# 2810_driverBoard.net
KiCad netlist of a schematic drawn in EasyEDA Pro
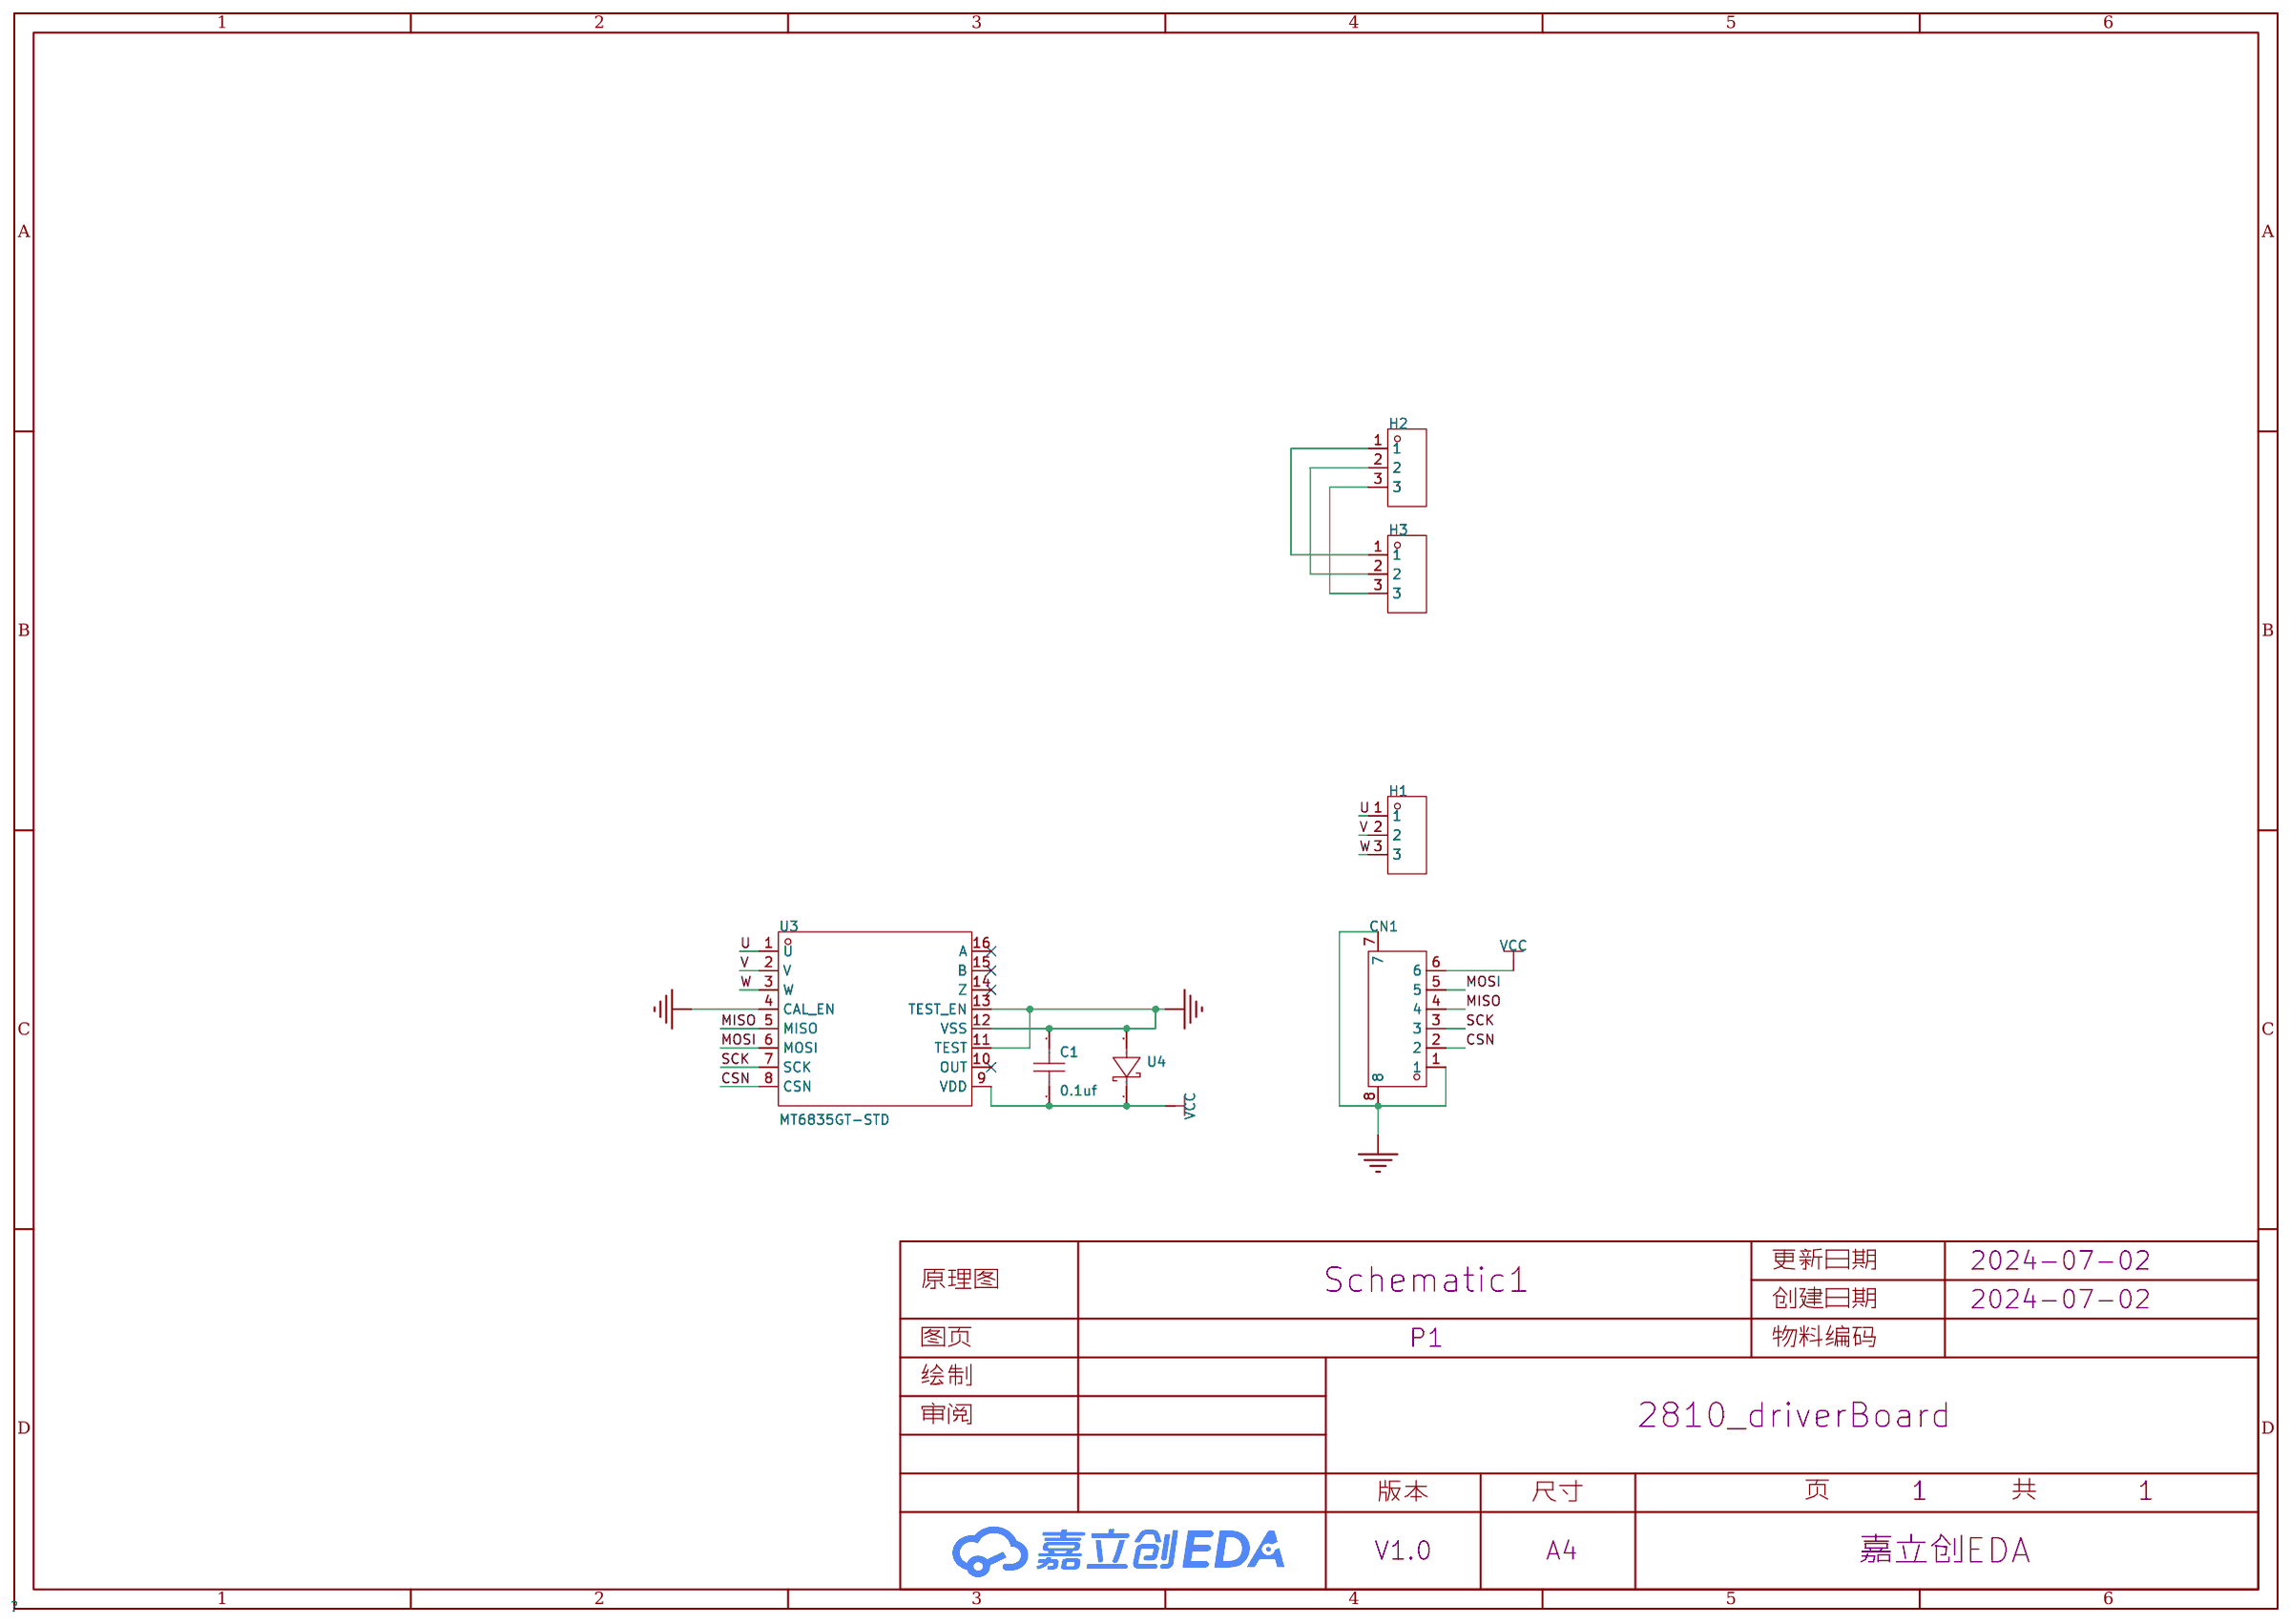
[diagram p0: schematic sheet]

(export (version "E")
  (design (tool "Eeschema 10.0.6"))
  (components
    (comp (ref "C1")
      (value "0.1uf")
      (footprint "easyedapro:C0603")
      (libsource (lib "easyedapro") (part "CapAcitance"))
    )
    (comp (ref "CN1")
      (value "M1010RS-06P")
      (footprint "easyedapro:CONN-SMD_M1010RS-06P")
      (description "插针结构:1x6P;间距:1mm;安装方式:卧贴;参考系列:-;总PIN数:6P;排数:1;每排PIN数:6;行距:-;额定电流:1A;工作温度范围:-25°C~+85°C;")
      (fields (field (name "Manufacturer") "XFCN(兴飞)"))
      (libsource (lib "easyedapro") (part "M1010RS-06P"))
    )
    (comp (ref "H1")
      (value "PZ254V-11-03P")
      (footprint "easyedapro:HDR-TH_3P-P2.54-V-M")
      (fields (field (name "Manufacturer") "XFCN(兴飞)"))
      (libsource (lib "easyedapro") (part "PZ254V-11-03P_C2937625"))
    )
    (comp (ref "H2")
      (value "PZ254V-11-03P")
      (footprint "easyedapro:HDR-TH_3P-P2.54-V-M")
      (fields (field (name "Manufacturer") "XFCN(兴飞)"))
      (libsource (lib "easyedapro") (part "PZ254V-11-03P_C2937625"))
    )
    (comp (ref "H3")
      (value "PZ254V-11-03P")
      (footprint "easyedapro:HDR-TH_3P-P2.54-V-M")
      (fields (field (name "Manufacturer") "XFCN(兴飞)"))
      (libsource (lib "easyedapro") (part "PZ254V-11-03P_C2937625"))
    )
    (comp (ref "U3")
      (value "MT6835GT-STD")
      (footprint "easyedapro:TSSOP-16_L5.0-W4.4-P0.65-LS6.4-BL")
      (fields (field (name "Manufacturer") "MagnTek(麦歌恩)"))
      (libsource (lib "easyedapro") (part "MT6835GT-STD"))
    )
    (comp (ref "U4")
      (value "PTVS6V0S1UR")
      (footprint "easyedapro:SOD-123_L2.7-W1.6-LS3.7-RD")
      (fields (field (name "Manufacturer") "FUXINSEMI(富芯森美)"))
      (libsource (lib "easyedapro") (part "PTVS6V0S1UR_C18723426"))
    )
  )
  (nets
    (net (code "1") (name "/CSN") (class "Default")
      (node (ref "CN1") (pin "2") (pinfunction "2_2") (pintype "unspecified"))
      (node (ref "U3") (pin "8") (pinfunction "CSN_8") (pintype "unspecified"))
    )
    (net (code "2") (name "/MISO") (class "Default")
      (node (ref "CN1") (pin "4") (pinfunction "4_4") (pintype "unspecified"))
      (node (ref "U3") (pin "5") (pinfunction "MISO_5") (pintype "unspecified"))
    )
    (net (code "3") (name "/MOSI") (class "Default")
      (node (ref "CN1") (pin "5") (pinfunction "5_5") (pintype "unspecified"))
      (node (ref "U3") (pin "6") (pinfunction "MOSI_6") (pintype "unspecified"))
    )
    (net (code "4") (name "/SCK") (class "Default")
      (node (ref "CN1") (pin "3") (pinfunction "3_3") (pintype "unspecified"))
      (node (ref "U3") (pin "7") (pinfunction "SCK_7") (pintype "unspecified"))
    )
    (net (code "5") (name "/U") (class "Default")
      (node (ref "H1") (pin "1") (pinfunction "1_1") (pintype "unspecified"))
      (node (ref "U3") (pin "1") (pinfunction "U_1") (pintype "unspecified"))
    )
    (net (code "6") (name "/V") (class "Default")
      (node (ref "H1") (pin "2") (pinfunction "2_2") (pintype "unspecified"))
      (node (ref "U3") (pin "2") (pinfunction "V_2") (pintype "unspecified"))
    )
    (net (code "7") (name "/W") (class "Default")
      (node (ref "H1") (pin "3") (pinfunction "3_3") (pintype "unspecified"))
      (node (ref "U3") (pin "3") (pinfunction "W_3") (pintype "unspecified"))
    )
    (net (code "8") (name "GND") (class "Default")
      (node (ref "C1") (pin "2") (pinfunction "2_2") (pintype "input"))
      (node (ref "CN1") (pin "1") (pinfunction "1_1") (pintype "unspecified"))
      (node (ref "CN1") (pin "7") (pinfunction "7_7") (pintype "unspecified"))
      (node (ref "CN1") (pin "8") (pinfunction "8_8") (pintype "unspecified"))
      (node (ref "U3") (pin "11") (pinfunction "TEST_11") (pintype "unspecified"))
      (node (ref "U3") (pin "12") (pinfunction "VSS_12") (pintype "unspecified"))
      (node (ref "U3") (pin "13") (pinfunction "TEST_EN_13") (pintype "unspecified"))
      (node (ref "U3") (pin "4") (pinfunction "CAL_EN_4") (pintype "unspecified"))
      (node (ref "U4") (pin "2") (pinfunction "A_2") (pintype "unspecified"))
    )
    (net (code "9") (name "Net-(H2-Pad1)") (class "Default")
      (node (ref "H2") (pin "1") (pinfunction "1_1") (pintype "unspecified"))
      (node (ref "H3") (pin "1") (pinfunction "1_1") (pintype "unspecified"))
    )
    (net (code "10") (name "Net-(H2-Pad2)") (class "Default")
      (node (ref "H2") (pin "2") (pinfunction "2_2") (pintype "unspecified"))
      (node (ref "H3") (pin "2") (pinfunction "2_2") (pintype "unspecified"))
    )
    (net (code "11") (name "Net-(H2-Pad3)") (class "Default")
      (node (ref "H2") (pin "3") (pinfunction "3_3") (pintype "unspecified"))
      (node (ref "H3") (pin "3") (pinfunction "3_3") (pintype "unspecified"))
    )
    (net (code "12") (name "VCC") (class "Default")
      (node (ref "C1") (pin "1") (pinfunction "1_1") (pintype "input"))
      (node (ref "CN1") (pin "6") (pinfunction "6_6") (pintype "unspecified"))
      (node (ref "U3") (pin "9") (pinfunction "VDD_9") (pintype "unspecified"))
      (node (ref "U4") (pin "1") (pinfunction "K_1") (pintype "unspecified"))
    )
    (net (code "13") (name "unconnected-(U3-A-Pad16)") (class "Default")
      (node (ref "U3") (pin "16") (pinfunction "A_16") (pintype "unspecified+no_connect"))
    )
    (net (code "14") (name "unconnected-(U3-B-Pad15)") (class "Default")
      (node (ref "U3") (pin "15") (pinfunction "B_15") (pintype "unspecified+no_connect"))
    )
    (net (code "15") (name "unconnected-(U3-OUT-Pad10)") (class "Default")
      (node (ref "U3") (pin "10") (pinfunction "OUT_10") (pintype "unspecified+no_connect"))
    )
    (net (code "16") (name "unconnected-(U3-Z-Pad14)") (class "Default")
      (node (ref "U3") (pin "14") (pinfunction "Z_14") (pintype "unspecified+no_connect"))
    )
  )
)
